# Deconstruction.net
KiCad netlist of a schematic drawn in EAGLE
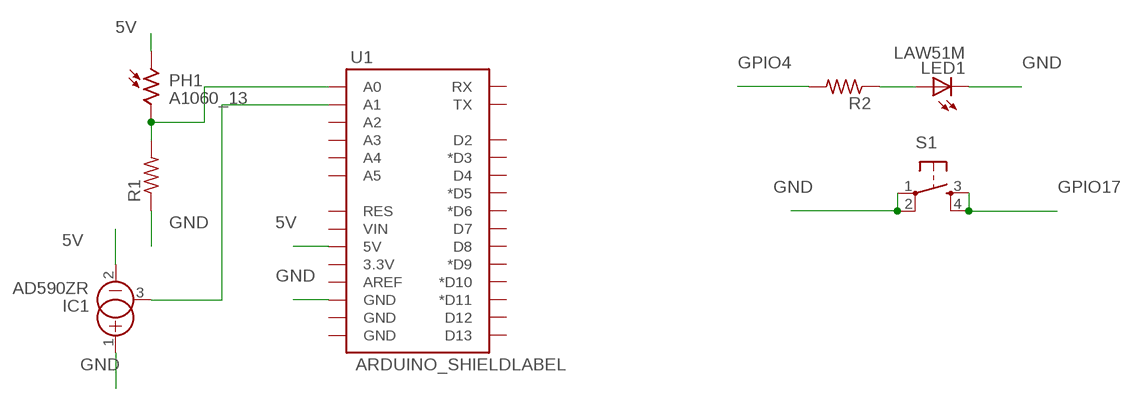
[diagram p0: schematic, sheet 1]

(export (version "E")
  (design (tool "Eeschema 10.0.6"))
  (components
    (comp (ref "IC1")
      (value "AD590ZR")
      (footprint "eagle-import:TO92")
      (libsource (lib "eagle-import") (part "AD590ZR"))
    )
    (comp (ref "LED1")
      (value "LAW51M")
      (footprint "eagle-import:W51")
      (libsource (lib "eagle-import") (part "W51MLA"))
    )
    (comp (ref "PH1")
      (value "A1060_13")
      (footprint "eagle-import:T0-46-A10XX")
      (libsource (lib "eagle-import") (part "A1060_13"))
    )
    (comp (ref "R1")
      (value "R-US_0411/12")
      (footprint "eagle-import:0411_12")
      (libsource (lib "eagle-import") (part "R-US_0411/12"))
    )
    (comp (ref "R2")
      (value "R-US_0411/12")
      (footprint "eagle-import:0411_12")
      (libsource (lib "eagle-import") (part "R-US_0411/12"))
    )
    (comp (ref "S1")
      (value "TAC_SWITCHPTH")
      (footprint "eagle-import:TACTILE-PTH")
      (libsource (lib "eagle-import") (part "TAC_SWITCHPTH"))
    )
    (comp (ref "U1")
      (value "ARDUINO_SHIELDLABEL")
      (footprint "eagle-import:DUEMILANOVE_SHIELD")
      (libsource (lib "eagle-import") (part "ARDUINO_SHIELDLABEL"))
    )
  )
  (nets
    (net (code "1") (name "/5V") (class "Default")
      (node (ref "IC1") (pin "2") (pinfunction "-_2") (pintype "input"))
      (node (ref "PH1") (pin "1") (pinfunction "1_1") (pintype "passive"))
      (node (ref "U1") (pin "5V") (pinfunction "5V_5V") (pintype "bidirectional"))
    )
    (net (code "2") (name "/GND") (class "Default")
      (node (ref "IC1") (pin "1") (pinfunction "+_1") (pintype "input"))
      (node (ref "LED1") (pin "C") (pinfunction "C_C") (pintype "passive"))
      (node (ref "R1") (pin "1") (pinfunction "1_1") (pintype "passive"))
      (node (ref "S1") (pin "1") (pinfunction "1_1") (pintype "passive"))
      (node (ref "S1") (pin "2") (pinfunction "2_2") (pintype "passive"))
      (node (ref "U1") (pin "GND@2") (pinfunction "GND_GND@2") (pintype "bidirectional"))
    )
    (net (code "3") (name "/GPIO4") (class "Default")
      (node (ref "R2") (pin "2") (pinfunction "2_2") (pintype "passive"))
    )
    (net (code "4") (name "/GPIO17") (class "Default")
      (node (ref "S1") (pin "3") (pinfunction "3_3") (pintype "passive"))
      (node (ref "S1") (pin "4") (pinfunction "4_4") (pintype "passive"))
    )
    (net (code "5") (name "Net-(IC1-CAN)") (class "Default")
      (node (ref "IC1") (pin "3") (pinfunction "CAN_3") (pintype "passive"))
      (node (ref "U1") (pin "A1") (pinfunction "A1_A1") (pintype "bidirectional"))
    )
    (net (code "6") (name "Net-(LED1-PadA)") (class "Default")
      (node (ref "LED1") (pin "A") (pinfunction "A_A") (pintype "passive"))
      (node (ref "R2") (pin "1") (pinfunction "1_1") (pintype "passive"))
    )
    (net (code "7") (name "Net-(PH1-Pad2)") (class "Default")
      (node (ref "PH1") (pin "2") (pinfunction "2_2") (pintype "passive"))
      (node (ref "R1") (pin "2") (pinfunction "2_2") (pintype "passive"))
      (node (ref "U1") (pin "A0") (pinfunction "A0_A0") (pintype "bidirectional"))
    )
    (net (code "8") (name "unconnected-(U1-*D3-PadD3)") (class "Default")
      (node (ref "U1") (pin "D3") (pinfunction "*D3_D3") (pintype "bidirectional"))
    )
    (net (code "9") (name "unconnected-(U1-*D5-PadD5)") (class "Default")
      (node (ref "U1") (pin "D5") (pinfunction "*D5_D5") (pintype "bidirectional"))
    )
    (net (code "10") (name "unconnected-(U1-*D6-PadD6)") (class "Default")
      (node (ref "U1") (pin "D6") (pinfunction "*D6_D6") (pintype "bidirectional"))
    )
    (net (code "11") (name "unconnected-(U1-*D9-PadD9)") (class "Default")
      (node (ref "U1") (pin "D9") (pinfunction "*D9_D9") (pintype "bidirectional"))
    )
    (net (code "12") (name "unconnected-(U1-*D10-PadD10)") (class "Default")
      (node (ref "U1") (pin "D10") (pinfunction "*D10_D10") (pintype "bidirectional"))
    )
    (net (code "13") (name "unconnected-(U1-*D11-PadD11)") (class "Default")
      (node (ref "U1") (pin "D11") (pinfunction "*D11_D11") (pintype "bidirectional"))
    )
    (net (code "14") (name "unconnected-(U1-GND-PadGND@0)") (class "Default")
      (node (ref "U1") (pin "GND@0") (pinfunction "GND_GND@0") (pintype "bidirectional"))
    )
    (net (code "15") (name "unconnected-(U1-GND-PadGND@1)") (class "Default")
      (node (ref "U1") (pin "GND@1") (pinfunction "GND_GND@1") (pintype "bidirectional"))
    )
    (net (code "16") (name "unconnected-(U1-Pad3.3V)") (class "Default")
      (node (ref "U1") (pin "3.3V") (pinfunction "3.3V_3.3V") (pintype "bidirectional"))
    )
    (net (code "17") (name "unconnected-(U1-PadA2)") (class "Default")
      (node (ref "U1") (pin "A2") (pinfunction "A2_A2") (pintype "bidirectional"))
    )
    (net (code "18") (name "unconnected-(U1-PadA3)") (class "Default")
      (node (ref "U1") (pin "A3") (pinfunction "A3_A3") (pintype "bidirectional"))
    )
    (net (code "19") (name "unconnected-(U1-PadA4)") (class "Default")
      (node (ref "U1") (pin "A4") (pinfunction "A4_A4") (pintype "bidirectional"))
    )
    (net (code "20") (name "unconnected-(U1-PadA5)") (class "Default")
      (node (ref "U1") (pin "A5") (pinfunction "A5_A5") (pintype "bidirectional"))
    )
    (net (code "21") (name "unconnected-(U1-PadAREF)") (class "Default")
      (node (ref "U1") (pin "AREF") (pinfunction "AREF_AREF") (pintype "bidirectional"))
    )
    (net (code "22") (name "unconnected-(U1-PadD2)") (class "Default")
      (node (ref "U1") (pin "D2") (pinfunction "D2_D2") (pintype "bidirectional"))
    )
    (net (code "23") (name "unconnected-(U1-PadD4)") (class "Default")
      (node (ref "U1") (pin "D4") (pinfunction "D4_D4") (pintype "bidirectional"))
    )
    (net (code "24") (name "unconnected-(U1-PadD7)") (class "Default")
      (node (ref "U1") (pin "D7") (pinfunction "D7_D7") (pintype "bidirectional"))
    )
    (net (code "25") (name "unconnected-(U1-PadD8)") (class "Default")
      (node (ref "U1") (pin "D8") (pinfunction "D8_D8") (pintype "bidirectional"))
    )
    (net (code "26") (name "unconnected-(U1-PadD12)") (class "Default")
      (node (ref "U1") (pin "D12") (pinfunction "D12_D12") (pintype "bidirectional"))
    )
    (net (code "27") (name "unconnected-(U1-PadD13)") (class "Default")
      (node (ref "U1") (pin "D13") (pinfunction "D13_D13") (pintype "bidirectional"))
    )
    (net (code "28") (name "unconnected-(U1-PadRES)") (class "Default")
      (node (ref "U1") (pin "RES") (pinfunction "RES_RES") (pintype "bidirectional"))
    )
    (net (code "29") (name "unconnected-(U1-PadRX)") (class "Default")
      (node (ref "U1") (pin "RX") (pinfunction "RX_RX") (pintype "bidirectional"))
    )
    (net (code "30") (name "unconnected-(U1-PadTX)") (class "Default")
      (node (ref "U1") (pin "TX") (pinfunction "TX_TX") (pintype "bidirectional"))
    )
    (net (code "31") (name "unconnected-(U1-PadVIN)") (class "Default")
      (node (ref "U1") (pin "VIN") (pinfunction "VIN_VIN") (pintype "bidirectional"))
    )
  )
)
